# FM_Module.net
KiCad netlist of a schematic drawn in Altium Designer
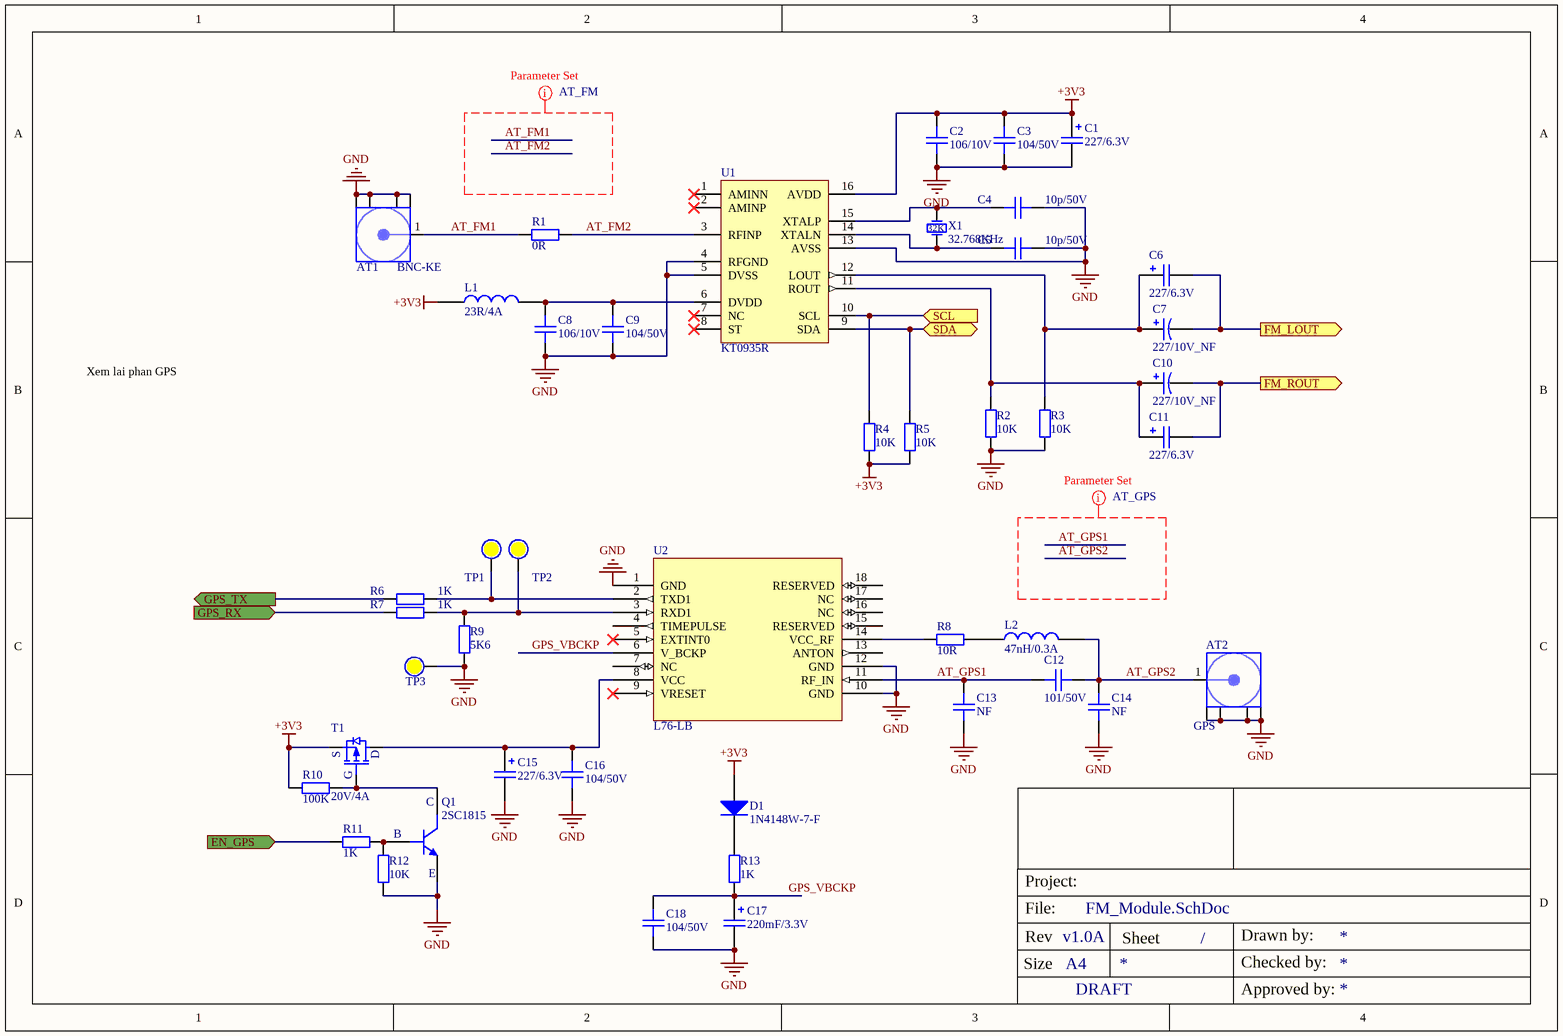
[diagram p0: FM_Module.SchDoc]

(export (version "E")
  (design (tool "Eeschema 10.0.6"))
  (components
    (comp (ref "AT1")
      (value "BNC-KE")
      (footprint "BNC-KE")
      (libsource (lib "04.Header-Connecter") (part "BNC-KE"))
    )
    (comp (ref "AT2")
      (value "GPS")
      (footprint "SMA-KE-20")
      (fields (field (name "MPN") "SMA-KE-20"))
      (libsource (lib "04.Header-Connecter") (part "SMA-KE-15"))
    )
    (comp (ref "C1")
      (value "227/6.3V")
      (footprint "CAP_TANTAL_1210(3528)")
      (description "CAP TANT POLY 220uF 20% 6.3V 3528 35mOhm ESR")
      (fields (field (name "MPN") "T520B227M006ATE035"))
      (libsource (lib "01.Passives") (part "T520B227M006ATE035"))
    )
    (comp (ref "C2")
      (value "106/10V")
      (footprint "CAPC-0603 (1608) - HD")
      (description "CAP CER 10uF 10% 10V X5R 0603")
      (fields (field (name "MPN") "CL10A106KP8NNNC"))
      (libsource (lib "01.Passives") (part "CL10A106KP8NNNC"))
    )
    (comp (ref "C3")
      (value "104/50V")
      (footprint "CAPC-0603 (1608) - HD")
      (description "CAP CER 0.1uF 50V 10% X7R 0603")
      (fields (field (name "MPN") "C0603C104K5RACTU"))
      (libsource (lib "01.Passives") (part "C0603C104K5RACTU"))
    )
    (comp (ref "C4")
      (value "10p/50V")
      (footprint "CAPC-0603 (1608) - HD")
      (description "CAP CER 10pF 5% 50V NP0 0603")
      (fields (field (name "MPN") "CL10C100JB8NNND"))
      (libsource (lib "01.Passives") (part "CL10C100JB8NNND"))
    )
    (comp (ref "C5")
      (value "10p/50V")
      (footprint "CAPC-0603 (1608) - HD")
      (description "CAP CER 10pF 5% 50V NP0 0603")
      (fields (field (name "MPN") "CL10C100JB8NNND"))
      (libsource (lib "01.Passives") (part "CL10C100JB8NNND"))
    )
    (comp (ref "C6")
      (value "227/6.3V")
      (footprint "CAP_TANTAL_1210(3528)")
      (description "CAP TANT POLY 220uF 20% 6.3V 3528 35mOhm ESR")
      (fields (field (name "MPN") "T520B227M006ATE035"))
      (libsource (lib "01.Passives") (part "T520B227M006ATE035"))
    )
    (comp (ref "C7")
      (value "227/10V_NF")
      (footprint "CAP_ALUM_D5.0_S2.0")
      (fields (field (name "MPN") "KM227M010D11RR0VH2FP0") (field (name "MFR") "CX(Dongguan Chengxing Elec)"))
      (libsource (lib "01.Passives 2") (part "KM227M010D11RR0VH2FP0"))
    )
    (comp (ref "C8")
      (value "106/10V")
      (footprint "CAPC-0603 (1608) - HD")
      (description "CAP CER 10uF 10% 10V X5R 0603")
      (fields (field (name "MPN") "CL10A106KP8NNNC"))
      (libsource (lib "01.Passives") (part "CL10A106KP8NNNC"))
    )
    (comp (ref "C9")
      (value "104/50V")
      (footprint "CAPC-0603 (1608) - HD")
      (description "CAP CER 0.1uF 50V 10% X7R 0603")
      (fields (field (name "MPN") "C0603C104K5RACTU"))
      (libsource (lib "01.Passives") (part "C0603C104K5RACTU"))
    )
    (comp (ref "C10")
      (value "227/10V_NF")
      (footprint "CAP_ALUM_D5.0_S2.0")
      (fields (field (name "MPN") "KM227M010D11RR0VH2FP0") (field (name "MFR") "CX(Dongguan Chengxing Elec)"))
      (libsource (lib "01.Passives 2") (part "KM227M010D11RR0VH2FP0"))
    )
    (comp (ref "C11")
      (value "227/6.3V")
      (footprint "CAP_TANTAL_1210(3528)")
      (description "CAP TANT POLY 220uF 20% 6.3V 3528 35mOhm ESR")
      (fields (field (name "MPN") "T520B227M006ATE035"))
      (libsource (lib "01.Passives") (part "T520B227M006ATE035"))
    )
    (comp (ref "C12")
      (value "101/50V")
      (footprint "CAPC-0603 (1608) - HD")
      (description "CAP CER 100pF 5% 50V C0G/NP0 0603")
      (fields (field (name "MPN") "GRM1885C1H101JA01D"))
      (libsource (lib "01.Passives 2") (part "GRM1885C1H101JA01D"))
    )
    (comp (ref "C13")
      (value "NF")
      (footprint "CAPC-0603 (1608) - HD")
      (description "CAP SMD, Not Fill, 0603")
      (libsource (lib "01.Passives") (part "CAPC NF 0603"))
    )
    (comp (ref "C14")
      (value "NF")
      (footprint "CAPC-0603 (1608) - HD")
      (description "CAP SMD, Not Fill, 0603")
      (libsource (lib "01.Passives") (part "CAPC NF 0603"))
    )
    (comp (ref "C15")
      (value "227/6.3V")
      (footprint "CAP_TANTAL_1210(3528)")
      (description "CAP TANT POLY 220uF 20% 6.3V 3528 35mOhm ESR")
      (fields (field (name "MPN") "T520B227M006ATE035"))
      (libsource (lib "01.Passives") (part "T520B227M006ATE035"))
    )
    (comp (ref "C16")
      (value "104/50V")
      (footprint "CAPC-0603 (1608) - HD")
      (description "CAP CER 0.1uF 50V 10% X7R 0603")
      (fields (field (name "MPN") "C0603C104K5RACTU"))
      (libsource (lib "01.Passives") (part "C0603C104K5RACTU"))
    )
    (comp (ref "C17")
      (value "220mF/3.3V")
      (footprint "CAP-SUPER-0.22F")
      (description "CAP 220mF SUPER -20% +80% 3.3V SMD")
      (fields (field (name "MPN") "DCK-3R3E224U-E"))
      (libsource (lib "01.Passives") (part "DCK-3R3E224U-E"))
    )
    (comp (ref "C18")
      (value "104/50V")
      (footprint "CAPC-0603 (1608) - HD")
      (description "CAP CER 0.1uF 50V 10% X7R 0603")
      (fields (field (name "MPN") "C0603C104K5RACTU"))
      (libsource (lib "01.Passives") (part "C0603C104K5RACTU"))
    )
    (comp (ref "D1")
      (value "1N4148W-7-F")
      (footprint "SOD-123")
      (description "Diode Standard 100V 300mA (DC) Surface Mount SOD-123")
      (libsource (lib "Library_Chip") (part "Diode 1N4148"))
    )
    (comp (ref "L1")
      (value "23R/4A")
      (footprint "IND-0603 (1608) - HD")
      (description "IND-FERRITE BEAD 23 OHM  4A 0603 1LN")
      (fields (field (name "MPN") "FBMJ1608HM230NT"))
      (libsource (lib "01.Passives") (part "FBMJ1608HM230NT"))
    )
    (comp (ref "L2")
      (value "47nH/0.3A")
      (footprint "IND-0603 (1608) - HD")
      (description "IND-FIXED 47nH 300mA 700 mOhm 0603")
      (fields (field (name "MPN") "HK160847NJ-T"))
      (libsource (lib "01.Passives") (part "HK160847NJ-T"))
    )
    (comp (ref "Q1")
      (value "2SC1815")
      (footprint "SOT23_3")
      (description "TRANS NPN 50V 0.15A SOT23-3")
      (libsource (lib "03.Semiconductor") (part "2SC1815"))
    )
    (comp (ref "R1")
      (value "0R")
      (footprint "RESC-0603 (1608) - HD")
      (description "RES SMD 0.0OHM JUMPER 1/10W 0603")
      (fields (field (name "MPN") "RC0603FR-070RL"))
      (libsource (lib "01.Passives") (part "RC0603FR-070RL"))
    )
    (comp (ref "R2")
      (value "10K")
      (footprint "RESC-0603 (1608) - HD")
      (description "RES SMD 10K OHM 1% 1/10W 0603")
      (fields (field (name "MPN") "RC0603FR-0710KL"))
      (libsource (lib "01.Passives") (part "RC0603FR-0710KL"))
    )
    (comp (ref "R3")
      (value "10K")
      (footprint "RESC-0603 (1608) - HD")
      (description "RES SMD 10K OHM 1% 1/10W 0603")
      (fields (field (name "MPN") "RC0603FR-0710KL"))
      (libsource (lib "01.Passives") (part "RC0603FR-0710KL"))
    )
    (comp (ref "R4")
      (value "10K")
      (footprint "RESC-0603 (1608) - HD")
      (description "RES SMD 10K OHM 1% 1/10W 0603")
      (fields (field (name "MPN") "RC0603FR-0710KL"))
      (libsource (lib "01.Passives") (part "RC0603FR-0710KL"))
    )
    (comp (ref "R5")
      (value "10K")
      (footprint "RESC-0603 (1608) - HD")
      (description "RES SMD 10K OHM 1% 1/10W 0603")
      (fields (field (name "MPN") "RC0603FR-0710KL"))
      (libsource (lib "01.Passives") (part "RC0603FR-0710KL"))
    )
    (comp (ref "R6")
      (value "1K")
      (footprint "RESC-0603 (1608) - HD")
      (description "RES SMD 1 KOHM 1% 1/10W 0603")
      (fields (field (name "MPN") "RC0603FR-071KL"))
      (libsource (lib "01.Passives") (part "RC0603FR-071KL"))
    )
    (comp (ref "R7")
      (value "1K")
      (footprint "RESC-0603 (1608) - HD")
      (description "RES SMD 1 KOHM 1% 1/10W 0603")
      (fields (field (name "MPN") "RC0603FR-071KL"))
      (libsource (lib "01.Passives") (part "RC0603FR-071KL"))
    )
    (comp (ref "R8")
      (value "10R")
      (footprint "RESC-0603 (1608) - HD")
      (description "RES SMD 10 OHM 1% 1/10W 0603")
      (fields (field (name "MPN") "RC0603FR-0710RL"))
      (libsource (lib "01.Passives") (part "RC0603FR-0710RL"))
    )
    (comp (ref "R9")
      (value "5K6")
      (footprint "RESC-0603 (1608) - HD")
      (description "RES SMD 5.6K OHM 1% 1/10W 0603")
      (fields (field (name "MPN") "RC0603FR-075K6L"))
      (libsource (lib "01.Passives") (part "RC0603FR-075K6L"))
    )
    (comp (ref "R10")
      (value "100K")
      (footprint "RESC-0603 (1608) - HD")
      (description "RES SMD 100K OHM 1% 1/10W 0603")
      (fields (field (name "MPN") "RC0603FR-07100KL"))
      (libsource (lib "01.Passives") (part "RC0603FR-07100KL"))
    )
    (comp (ref "R11")
      (value "1K")
      (footprint "RESC-0603 (1608) - HD")
      (description "RES SMD 1 KOHM 1% 1/10W 0603")
      (fields (field (name "MPN") "RC0603FR-071KL"))
      (libsource (lib "01.Passives") (part "RC0603FR-071KL"))
    )
    (comp (ref "R12")
      (value "10K")
      (footprint "RESC-0603 (1608) - HD")
      (description "RES SMD 10K OHM 1% 1/10W 0603")
      (fields (field (name "MPN") "RC0603FR-0710KL"))
      (libsource (lib "01.Passives") (part "RC0603FR-0710KL"))
    )
    (comp (ref "R13")
      (value "1K")
      (footprint "RESC-0603 (1608) - HD")
      (description "RES SMD 1 KOHM 1% 1/10W 0603")
      (fields (field (name "MPN") "RC0603FR-071KL"))
      (libsource (lib "") (part "RC0603FR-071KL_1"))
    )
    (comp (ref "T1")
      (value "20V/4A")
      (footprint "SOT23_3")
      (description "MOSFET P-CH 20V 4A SOT23")
      (fields (field (name "MPN") "AO3415") (field (name "MFR") "Alpha & Omega Semiconductor Inc."))
      (libsource (lib "03.Semiconductor") (part "AO3415"))
    )
    (comp (ref "TP1")
      (value "~")
      (footprint "Test Point 1 Side")
      (description "Test Point")
      (libsource (lib "") (part "Test Point_1"))
    )
    (comp (ref "TP2")
      (value "~")
      (footprint "Test Point 1 Side")
      (description "Test Point")
      (libsource (lib "") (part "Test Point_1"))
    )
    (comp (ref "TP3")
      (value "~")
      (footprint "Test Point 1 Side")
      (description "Test Point")
      (libsource (lib "08.Miscellaneous") (part "Test Point"))
    )
    (comp (ref "U1")
      (value "KT0935R")
      (footprint "KT0935R")
      (description "RF RX AM/FM RECEIVER")
      (libsource (lib "05.IC") (part "KT0935R"))
    )
    (comp (ref "U2")
      (value "L76-LB")
      (footprint "GPS.L7x")
      (description "GPS Module L76-LB, Quectel")
      (fields (field (name "MFR") "Quectel"))
      (libsource (lib "05.IC") (part "Quectel L76-LB"))
    )
    (comp (ref "X1")
      (value "32.768KHz")
      (footprint "CRYSTAL_ABS06 2x1.2mm")
      (description "CRYSTAL 32.7680KHZ 4pF SMD")
      (fields (field (name "MPN") "ABS06-107-32.768kHz-T"))
      (libsource (lib "01.Passives") (part "ABS06-107-32.768kHz-T"))
    )
  )
  (nets
    (net (code "1") (name "+3V3") (class "Default")
      (node (ref "C1") (pin "1") (pinfunction "1_1") (pintype "passive"))
      (node (ref "C2") (pin "2") (pinfunction "2_2") (pintype "passive"))
      (node (ref "C3") (pin "2") (pinfunction "2_2") (pintype "passive"))
      (node (ref "D1") (pin "1") (pinfunction "A_1") (pintype "passive"))
      (node (ref "L1") (pin "1") (pinfunction "1_1") (pintype "passive"))
      (node (ref "R10") (pin "1") (pinfunction "1_1") (pintype "passive"))
      (node (ref "R4") (pin "1") (pinfunction "1_1") (pintype "passive"))
      (node (ref "R5") (pin "1") (pinfunction "1_1") (pintype "passive"))
      (node (ref "T1") (pin "2") (pinfunction "S_2") (pintype "passive"))
      (node (ref "U1") (pin "16") (pinfunction "AVDD_16") (pintype "passive"))
    )
    (net (code "2") (name "/AT_FM1") (class "Default")
      (node (ref "AT1") (pin "1") (pinfunction "Signal_1") (pintype "passive"))
      (node (ref "R1") (pin "1") (pinfunction "1_1") (pintype "passive"))
    )
    (net (code "3") (name "/AT_FM2") (class "Default")
      (node (ref "R1") (pin "2") (pinfunction "2_2") (pintype "passive"))
      (node (ref "U1") (pin "3") (pinfunction "RFINP_3") (pintype "passive"))
    )
    (net (code "4") (name "/AT_GPS1") (class "Default")
      (node (ref "C12") (pin "1") (pinfunction "1_1") (pintype "passive"))
      (node (ref "C13") (pin "2") (pinfunction "2_2") (pintype "passive"))
      (node (ref "U2") (pin "11") (pinfunction "RF_IN_11") (pintype "input"))
    )
    (net (code "5") (name "/AT_GPS2") (class "Default")
      (node (ref "AT2") (pin "1") (pinfunction "Signal_1") (pintype "passive"))
      (node (ref "C12") (pin "2") (pinfunction "2_2") (pintype "passive"))
      (node (ref "C14") (pin "2") (pinfunction "2_2") (pintype "passive"))
      (node (ref "L2") (pin "2") (pinfunction "2_2") (pintype "passive"))
    )
    (net (code "6") (name "/EN_GPS") (class "Default")
      (node (ref "R11") (pin "1") (pinfunction "1_1") (pintype "passive"))
    )
    (net (code "7") (name "/FM_LOUT") (class "Default")
      (node (ref "C6") (pin "2") (pinfunction "2_2") (pintype "passive"))
      (node (ref "C7") (pin "2") (pinfunction "2_2") (pintype "passive"))
    )
    (net (code "8") (name "/FM_ROUT") (class "Default")
      (node (ref "C10") (pin "2") (pinfunction "2_2") (pintype "passive"))
      (node (ref "C11") (pin "2") (pinfunction "2_2") (pintype "passive"))
    )
    (net (code "9") (name "/GPS_RX") (class "Default")
      (node (ref "R7") (pin "1") (pinfunction "1_1") (pintype "passive"))
    )
    (net (code "10") (name "/GPS_TX") (class "Default")
      (node (ref "R6") (pin "1") (pinfunction "1_1") (pintype "passive"))
    )
    (net (code "11") (name "/GPS_VBCKP") (class "Default")
      (node (ref "C17") (pin "1") (pinfunction "1_1") (pintype "passive"))
      (node (ref "C18") (pin "2") (pinfunction "2_2") (pintype "passive"))
      (node (ref "R13") (pin "1") (pinfunction "1_1") (pintype "passive"))
      (node (ref "U2") (pin "6") (pinfunction "V_BCKP_6") (pintype "power_in"))
    )
    (net (code "12") (name "/SCL") (class "Default")
      (node (ref "R4") (pin "2") (pinfunction "2_2") (pintype "passive"))
      (node (ref "U1") (pin "10") (pinfunction "SCL_10") (pintype "passive"))
    )
    (net (code "13") (name "/SDA") (class "Default")
      (node (ref "R5") (pin "2") (pinfunction "2_2") (pintype "passive"))
      (node (ref "U1") (pin "9") (pinfunction "SDA_9") (pintype "passive"))
    )
    (net (code "14") (name "GND") (class "Default")
      (node (ref "AT1") (pin "2") (pinfunction "2_2") (pintype "power_in"))
      (node (ref "AT2") (pin "2") (pinfunction "2_2") (pintype "power_in"))
      (node (ref "C1") (pin "2") (pinfunction "2_2") (pintype "passive"))
      (node (ref "C13") (pin "1") (pinfunction "1_1") (pintype "passive"))
      (node (ref "C14") (pin "1") (pinfunction "1_1") (pintype "passive"))
      (node (ref "C15") (pin "2") (pinfunction "2_2") (pintype "passive"))
      (node (ref "C16") (pin "1") (pinfunction "1_1") (pintype "passive"))
      (node (ref "C17") (pin "2") (pinfunction "2_2") (pintype "passive"))
      (node (ref "C18") (pin "1") (pinfunction "1_1") (pintype "passive"))
      (node (ref "C2") (pin "1") (pinfunction "1_1") (pintype "passive"))
      (node (ref "C3") (pin "1") (pinfunction "1_1") (pintype "passive"))
      (node (ref "C4") (pin "2") (pinfunction "2_2") (pintype "passive"))
      (node (ref "C5") (pin "2") (pinfunction "2_2") (pintype "passive"))
      (node (ref "C8") (pin "1") (pinfunction "1_1") (pintype "passive"))
      (node (ref "C9") (pin "1") (pinfunction "1_1") (pintype "passive"))
      (node (ref "Q1") (pin "2") (pinfunction "E_2") (pintype "passive"))
      (node (ref "R12") (pin "1") (pinfunction "1_1") (pintype "passive"))
      (node (ref "R2") (pin "1") (pinfunction "1_1") (pintype "passive"))
      (node (ref "R3") (pin "1") (pinfunction "1_1") (pintype "passive"))
      (node (ref "R9") (pin "1") (pinfunction "1_1") (pintype "passive"))
      (node (ref "TP3") (pin "0") (pinfunction "0_0") (pintype "passive"))
      (node (ref "U1") (pin "13") (pinfunction "AVSS_13") (pintype "passive"))
      (node (ref "U1") (pin "4") (pinfunction "RFGND_4") (pintype "passive"))
      (node (ref "U1") (pin "5") (pinfunction "DVSS_5") (pintype "passive"))
      (node (ref "U2") (pin "1") (pinfunction "GND_1") (pintype "power_in"))
      (node (ref "U2") (pin "10") (pinfunction "GND_10") (pintype "power_in"))
      (node (ref "U2") (pin "12") (pinfunction "GND_12") (pintype "power_in"))
    )
    (net (code "15") (name "Net-(D1-K)") (class "Default")
      (node (ref "D1") (pin "2") (pinfunction "K_2") (pintype "passive"))
      (node (ref "R13") (pin "2") (pinfunction "2_2") (pintype "passive"))
    )
    (net (code "16") (name "Net-(L2-Pad1)") (class "Default")
      (node (ref "L2") (pin "1") (pinfunction "1_1") (pintype "passive"))
      (node (ref "R8") (pin "2") (pinfunction "2_2") (pintype "passive"))
    )
    (net (code "17") (name "Net-(Q1-B)") (class "Default")
      (node (ref "Q1") (pin "1") (pinfunction "B_1") (pintype "passive"))
      (node (ref "R11") (pin "2") (pinfunction "2_2") (pintype "passive"))
      (node (ref "R12") (pin "2") (pinfunction "2_2") (pintype "passive"))
    )
    (net (code "18") (name "Net-(Q1-C)") (class "Default")
      (node (ref "Q1") (pin "3") (pinfunction "C_3") (pintype "passive"))
      (node (ref "R10") (pin "2") (pinfunction "2_2") (pintype "passive"))
      (node (ref "T1") (pin "1") (pinfunction "G_1") (pintype "passive"))
    )
    (net (code "19") (name "Net-(T1-D)") (class "Default")
      (node (ref "C15") (pin "1") (pinfunction "1_1") (pintype "passive"))
      (node (ref "C16") (pin "2") (pinfunction "2_2") (pintype "passive"))
      (node (ref "T1") (pin "3") (pinfunction "D_3") (pintype "passive"))
      (node (ref "U2") (pin "8") (pinfunction "VCC_8") (pintype "power_in"))
    )
    (net (code "20") (name "Net-(U1-DVDD)") (class "Default")
      (node (ref "C8") (pin "2") (pinfunction "2_2") (pintype "passive"))
      (node (ref "C9") (pin "2") (pinfunction "2_2") (pintype "passive"))
      (node (ref "L1") (pin "2") (pinfunction "2_2") (pintype "passive"))
      (node (ref "U1") (pin "6") (pinfunction "DVDD_6") (pintype "passive"))
    )
    (net (code "21") (name "Net-(U1-LOUT)") (class "Default")
      (node (ref "C6") (pin "1") (pinfunction "1_1") (pintype "passive"))
      (node (ref "C7") (pin "1") (pinfunction "1_1") (pintype "passive"))
      (node (ref "R3") (pin "2") (pinfunction "2_2") (pintype "passive"))
      (node (ref "U1") (pin "12") (pinfunction "LOUT_12") (pintype "output"))
    )
    (net (code "22") (name "Net-(U1-ROUT)") (class "Default")
      (node (ref "C10") (pin "1") (pinfunction "1_1") (pintype "passive"))
      (node (ref "C11") (pin "1") (pinfunction "1_1") (pintype "passive"))
      (node (ref "R2") (pin "2") (pinfunction "2_2") (pintype "passive"))
      (node (ref "U1") (pin "11") (pinfunction "ROUT_11") (pintype "output"))
    )
    (net (code "23") (name "Net-(U1-XTALN)") (class "Default")
      (node (ref "C5") (pin "1") (pinfunction "1_1") (pintype "passive"))
      (node (ref "U1") (pin "14") (pinfunction "XTALN_14") (pintype "passive"))
      (node (ref "X1") (pin "2") (pinfunction "OSC2_2") (pintype "passive"))
    )
    (net (code "24") (name "Net-(U1-XTALP)") (class "Default")
      (node (ref "C4") (pin "1") (pinfunction "1_1") (pintype "passive"))
      (node (ref "U1") (pin "15") (pinfunction "XTALP_15") (pintype "passive"))
      (node (ref "X1") (pin "1") (pinfunction "OSC1_1") (pintype "passive"))
    )
    (net (code "25") (name "Net-(U2-RXD1)") (class "Default")
      (node (ref "R7") (pin "2") (pinfunction "2_2") (pintype "passive"))
      (node (ref "R9") (pin "2") (pinfunction "2_2") (pintype "passive"))
      (node (ref "TP2") (pin "0") (pinfunction "0_0") (pintype "passive"))
      (node (ref "U2") (pin "3") (pinfunction "RXD1_3") (pintype "input"))
    )
    (net (code "26") (name "Net-(U2-TXD1)") (class "Default")
      (node (ref "R6") (pin "2") (pinfunction "2_2") (pintype "passive"))
      (node (ref "TP1") (pin "0") (pinfunction "0_0") (pintype "passive"))
      (node (ref "U2") (pin "2") (pinfunction "TXD1_2") (pintype "output"))
    )
    (net (code "27") (name "Net-(U2-VCC_RF)") (class "Default")
      (node (ref "R8") (pin "1") (pinfunction "1_1") (pintype "passive"))
      (node (ref "U2") (pin "14") (pinfunction "VCC_RF_14") (pintype "power_in"))
    )
    (net (code "28") (name "unconnected-(U1-AMINN-Pad1)") (class "Default")
      (node (ref "U1") (pin "1") (pinfunction "AMINN_1") (pintype "passive+no_connect"))
    )
    (net (code "29") (name "unconnected-(U1-AMINP-Pad2)") (class "Default")
      (node (ref "U1") (pin "2") (pinfunction "AMINP_2") (pintype "passive+no_connect"))
    )
    (net (code "30") (name "unconnected-(U1-NC-Pad7)") (class "Default")
      (node (ref "U1") (pin "7") (pinfunction "NC_7") (pintype "passive+no_connect"))
    )
    (net (code "31") (name "unconnected-(U1-ST-Pad8)") (class "Default")
      (node (ref "U1") (pin "8") (pinfunction "ST_8") (pintype "passive+no_connect"))
    )
    (net (code "32") (name "unconnected-(U2-ANTON-Pad13)") (class "Default")
      (node (ref "U2") (pin "13") (pinfunction "ANTON_13") (pintype "output"))
    )
    (net (code "33") (name "unconnected-(U2-EXTINT0-Pad5)") (class "Default")
      (node (ref "U2") (pin "5") (pinfunction "EXTINT0_5") (pintype "input+no_connect"))
    )
    (net (code "34") (name "unconnected-(U2-NC-Pad7)") (class "Default")
      (node (ref "U2") (pin "7") (pinfunction "NC_7") (pintype "bidirectional"))
    )
    (net (code "35") (name "unconnected-(U2-NC-Pad16)") (class "Default")
      (node (ref "U2") (pin "16") (pinfunction "NC_16") (pintype "bidirectional"))
    )
    (net (code "36") (name "unconnected-(U2-NC-Pad17)") (class "Default")
      (node (ref "U2") (pin "17") (pinfunction "NC_17") (pintype "bidirectional"))
    )
    (net (code "37") (name "unconnected-(U2-RESERVED-Pad15)") (class "Default")
      (node (ref "U2") (pin "15") (pinfunction "RESERVED_15") (pintype "bidirectional"))
    )
    (net (code "38") (name "unconnected-(U2-RESERVED-Pad18)") (class "Default")
      (node (ref "U2") (pin "18") (pinfunction "RESERVED_18") (pintype "bidirectional"))
    )
    (net (code "39") (name "unconnected-(U2-TIMEPULSE-Pad4)") (class "Default")
      (node (ref "U2") (pin "4") (pinfunction "TIMEPULSE_4") (pintype "output"))
    )
    (net (code "40") (name "unconnected-(U2-VRESET-Pad9)") (class "Default")
      (node (ref "U2") (pin "9") (pinfunction "VRESET_9") (pintype "input+no_connect"))
    )
  )
)
